# IRAMX-drv-v2.net
KiCad netlist of a schematic drawn in EAGLE
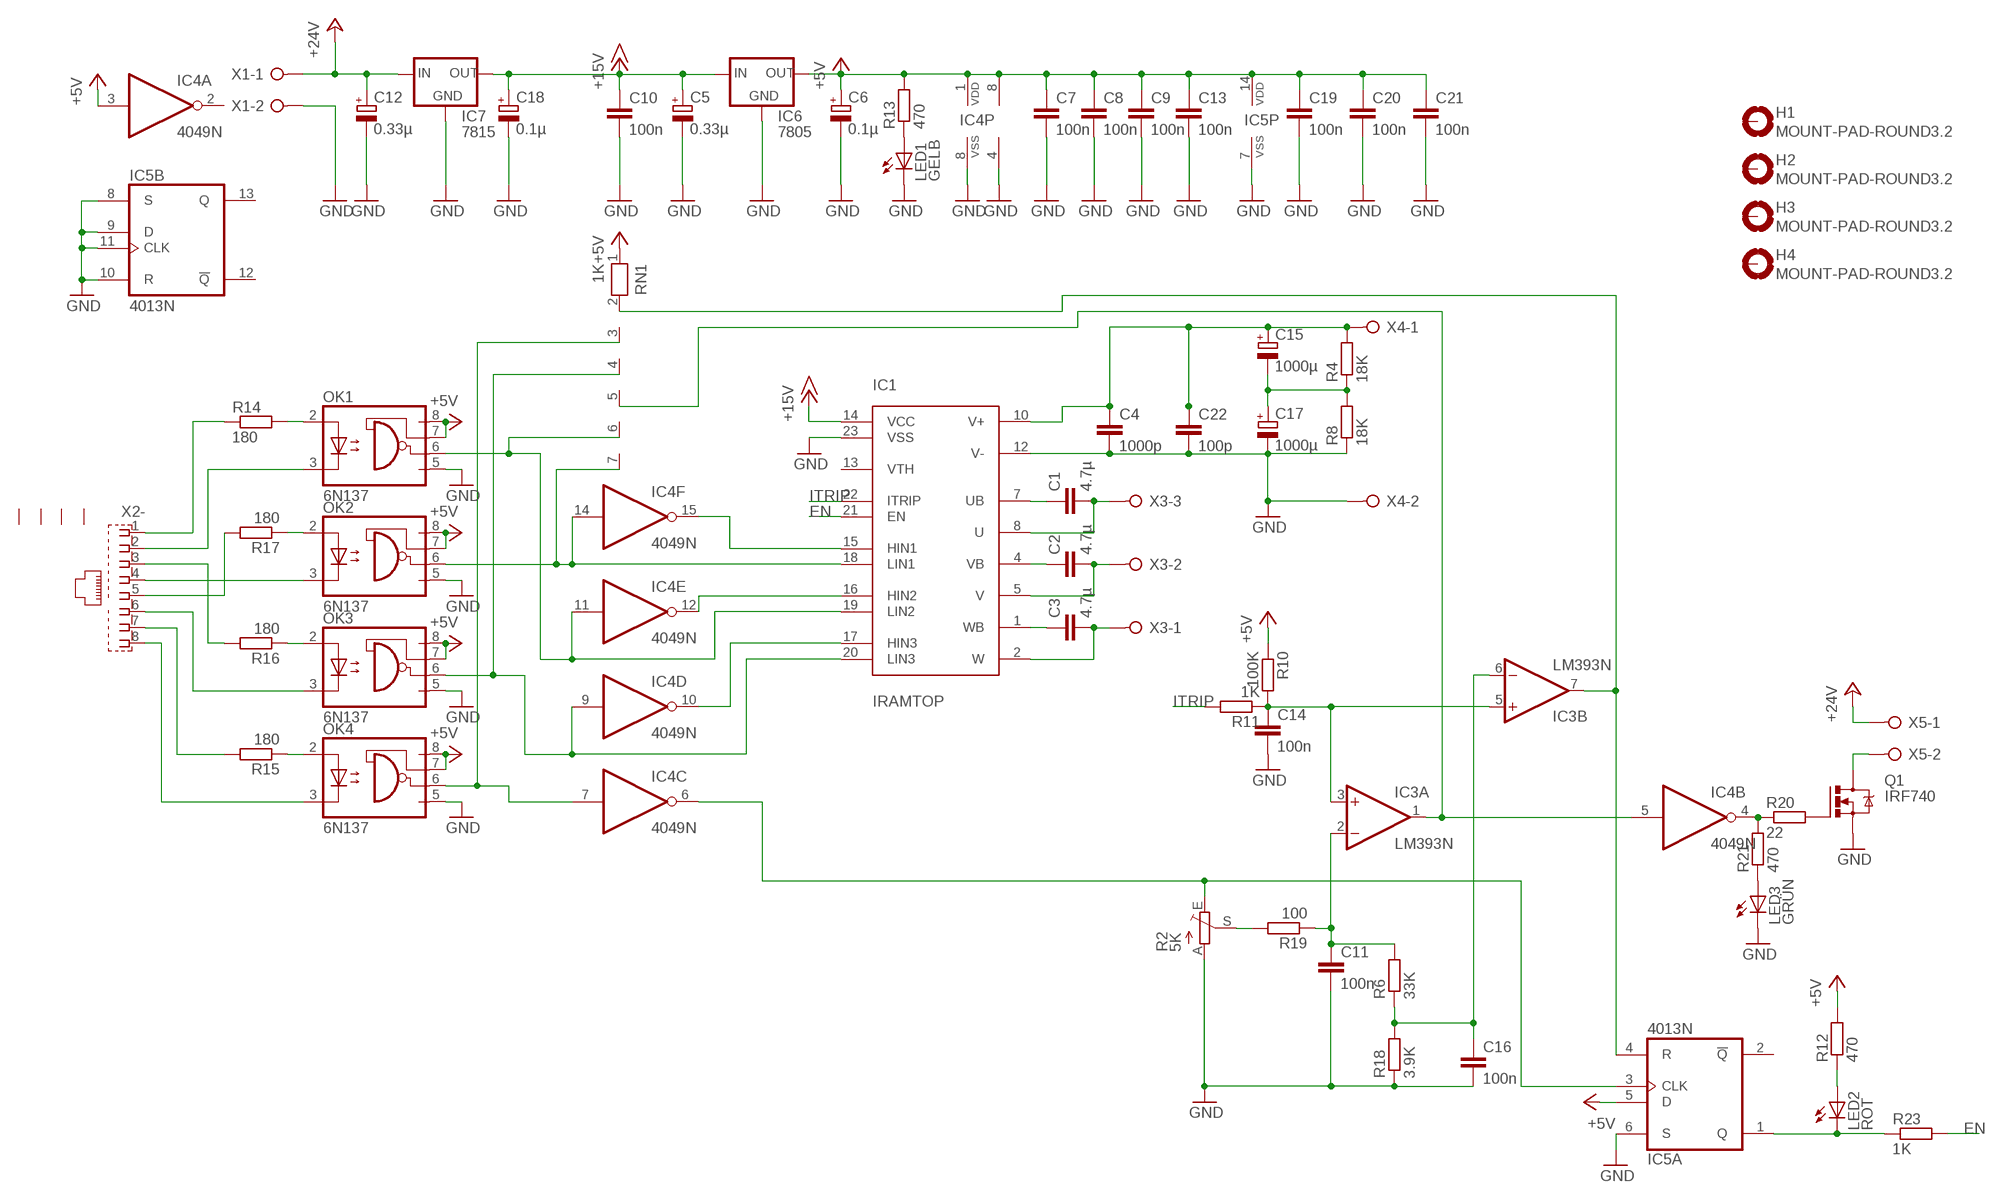
[diagram p0: schematic, sheet 1]

(export (version "E")
  (design (tool "Eeschema 10.0.6"))
  (components
    (comp (ref "C1")
      (value "4.7µ")
      (footprint "eagle-import:C5B7.2")
      (libsource (lib "eagle-import") (part "C5/7.2"))
    )
    (comp (ref "C2")
      (value "4.7µ")
      (footprint "eagle-import:C5B7.2")
      (libsource (lib "eagle-import") (part "C5/7.2"))
    )
    (comp (ref "C3")
      (value "4.7µ")
      (footprint "eagle-import:C5B7.2")
      (libsource (lib "eagle-import") (part "C5/7.2"))
    )
    (comp (ref "C4")
      (value "1000p")
      (footprint "eagle-import:C5B5")
      (libsource (lib "eagle-import") (part "C5/5"))
    )
    (comp (ref "C5")
      (value "0.33µ")
      (footprint "eagle-import:E2,5-5")
      (libsource (lib "eagle-import") (part "CPOL-EUE2.5-5"))
    )
    (comp (ref "C6")
      (value "0.1µ")
      (footprint "eagle-import:E2,5-5")
      (libsource (lib "eagle-import") (part "CPOL-EUE2.5-5"))
    )
    (comp (ref "C7")
      (value "100n")
      (footprint "eagle-import:C050-025X075")
      (libsource (lib "eagle-import") (part "C-EU050-025X075"))
    )
    (comp (ref "C8")
      (value "100n")
      (footprint "eagle-import:C050-025X075")
      (libsource (lib "eagle-import") (part "C-EU050-025X075"))
    )
    (comp (ref "C9")
      (value "100n")
      (footprint "eagle-import:C050-025X075")
      (libsource (lib "eagle-import") (part "C-EU050-025X075"))
    )
    (comp (ref "C10")
      (value "100n")
      (footprint "eagle-import:C050-025X075")
      (libsource (lib "eagle-import") (part "C-EU050-025X075"))
    )
    (comp (ref "C11")
      (value "100n")
      (footprint "eagle-import:C050-025X075")
      (libsource (lib "eagle-import") (part "C-EU050-025X075"))
    )
    (comp (ref "C12")
      (value "0.33µ")
      (footprint "eagle-import:E2,5-5")
      (libsource (lib "eagle-import") (part "CPOL-EUE2.5-5"))
    )
    (comp (ref "C13")
      (value "100n")
      (footprint "eagle-import:C050-025X075")
      (libsource (lib "eagle-import") (part "C-EU050-025X075"))
    )
    (comp (ref "C14")
      (value "100n")
      (footprint "eagle-import:C050-025X075")
      (libsource (lib "eagle-import") (part "C-EU050-025X075"))
    )
    (comp (ref "C15")
      (value "1000µ")
      (footprint "eagle-import:EB25D")
      (libsource (lib "eagle-import") (part "CPOL-EUE10-25"))
    )
    (comp (ref "C16")
      (value "100n")
      (footprint "eagle-import:C050-025X075")
      (libsource (lib "eagle-import") (part "C-EU050-025X075"))
    )
    (comp (ref "C17")
      (value "1000µ")
      (footprint "eagle-import:EB25D")
      (libsource (lib "eagle-import") (part "CPOL-EUE10-25"))
    )
    (comp (ref "C18")
      (value "0.1µ")
      (footprint "eagle-import:E2,5-5")
      (libsource (lib "eagle-import") (part "CPOL-EUE2.5-5"))
    )
    (comp (ref "C19")
      (value "100n")
      (footprint "eagle-import:C050-025X075")
      (libsource (lib "eagle-import") (part "C-EU050-025X075"))
    )
    (comp (ref "C20")
      (value "100n")
      (footprint "eagle-import:C050-025X075")
      (libsource (lib "eagle-import") (part "C-EU050-025X075"))
    )
    (comp (ref "C21")
      (value "100n")
      (footprint "eagle-import:C050-025X075")
      (libsource (lib "eagle-import") (part "C-EU050-025X075"))
    )
    (comp (ref "C22")
      (value "100p")
      (footprint "eagle-import:C150-054X183")
      (libsource (lib "eagle-import") (part "C-EU150-054X183"))
    )
    (comp (ref "H1")
      (value "MOUNT-PAD-ROUND3.2")
      (footprint "eagle-import:3,2-PAD")
      (libsource (lib "eagle-import") (part "MOUNT-PAD-ROUND3.2"))
    )
    (comp (ref "H2")
      (value "MOUNT-PAD-ROUND3.2")
      (footprint "eagle-import:3,2-PAD")
      (libsource (lib "eagle-import") (part "MOUNT-PAD-ROUND3.2"))
    )
    (comp (ref "H3")
      (value "MOUNT-PAD-ROUND3.2")
      (footprint "eagle-import:3,2-PAD")
      (libsource (lib "eagle-import") (part "MOUNT-PAD-ROUND3.2"))
    )
    (comp (ref "H4")
      (value "MOUNT-PAD-ROUND3.2")
      (footprint "eagle-import:3,2-PAD")
      (libsource (lib "eagle-import") (part "MOUNT-PAD-ROUND3.2"))
    )
    (comp (ref "IC1")
      (value "IRAMTOP")
      (footprint "eagle-import:SIP23_TOP")
      (libsource (lib "eagle-import") (part "IRAMTOP"))
    )
    (comp (ref "IC3")
      (value "LM393N")
      (footprint "eagle-import:DIL08")
      (libsource (lib "eagle-import") (part "LM393N"))
    )
    (comp (ref "IC4")
      (value "4049N")
      (footprint "eagle-import:DIL16")
      (libsource (lib "eagle-import") (part "4049N"))
    )
    (comp (ref "IC5")
      (value "4013N")
      (footprint "eagle-import:DIL14")
      (libsource (lib "eagle-import") (part "4013N"))
    )
    (comp (ref "IC6")
      (value "7805")
      (footprint "eagle-import:78XXS")
      (libsource (lib "eagle-import") (part "78XXS"))
    )
    (comp (ref "IC7")
      (value "7815")
      (footprint "eagle-import:78XXS")
      (libsource (lib "eagle-import") (part "78XXS"))
    )
    (comp (ref "LED1")
      (value "GELB")
      (footprint "eagle-import:LED5MM")
      (libsource (lib "eagle-import") (part "LED5MM"))
    )
    (comp (ref "LED2")
      (value "ROT")
      (footprint "eagle-import:LED5MM")
      (libsource (lib "eagle-import") (part "LED5MM"))
    )
    (comp (ref "LED3")
      (value "GRÜN")
      (footprint "eagle-import:LED5MM")
      (libsource (lib "eagle-import") (part "LED5MM"))
    )
    (comp (ref "OK1")
      (value "6N137")
      (footprint "eagle-import:DIL08")
      (libsource (lib "eagle-import") (part "6N137"))
    )
    (comp (ref "OK2")
      (value "6N137")
      (footprint "eagle-import:DIL08")
      (libsource (lib "eagle-import") (part "6N137"))
    )
    (comp (ref "OK3")
      (value "6N137")
      (footprint "eagle-import:DIL08")
      (libsource (lib "eagle-import") (part "6N137"))
    )
    (comp (ref "OK4")
      (value "6N137")
      (footprint "eagle-import:DIL08")
      (libsource (lib "eagle-import") (part "6N137"))
    )
    (comp (ref "Q1")
      (value "IRF740")
      (footprint "eagle-import:TO220BV")
      (libsource (lib "eagle-import") (part "IRF740"))
    )
    (comp (ref "R2")
      (value "5K")
      (footprint "eagle-import:CA6V")
      (libsource (lib "eagle-import") (part "TRIM_EU-CA6V"))
    )
    (comp (ref "R4")
      (value "18K")
      (footprint "eagle-import:CER")
      (libsource (lib "eagle-import") (part "R-EU_"))
    )
    (comp (ref "R6")
      (value "33K")
      (footprint "eagle-import:0204_7")
      (libsource (lib "eagle-import") (part "R-EU_0204/7"))
    )
    (comp (ref "R8")
      (value "18K")
      (footprint "eagle-import:CER")
      (libsource (lib "eagle-import") (part "R-EU_"))
    )
    (comp (ref "R10")
      (value "100K")
      (footprint "eagle-import:0204_7")
      (libsource (lib "eagle-import") (part "R-EU_0204/7"))
    )
    (comp (ref "R11")
      (value "1K")
      (footprint "eagle-import:0204_7")
      (libsource (lib "eagle-import") (part "R-EU_0204/7"))
    )
    (comp (ref "R12")
      (value "470")
      (footprint "eagle-import:0204_7")
      (libsource (lib "eagle-import") (part "R-EU_0204/7"))
    )
    (comp (ref "R13")
      (value "470")
      (footprint "eagle-import:0204_7")
      (libsource (lib "eagle-import") (part "R-EU_0204/7"))
    )
    (comp (ref "R14")
      (value "180")
      (footprint "eagle-import:0204V")
      (libsource (lib "eagle-import") (part "R-EU_0204/2V"))
    )
    (comp (ref "R15")
      (value "180")
      (footprint "eagle-import:0204V")
      (libsource (lib "eagle-import") (part "R-EU_0204/2V"))
    )
    (comp (ref "R16")
      (value "180")
      (footprint "eagle-import:0204V")
      (libsource (lib "eagle-import") (part "R-EU_0204/2V"))
    )
    (comp (ref "R17")
      (value "180")
      (footprint "eagle-import:0204V")
      (libsource (lib "eagle-import") (part "R-EU_0204/2V"))
    )
    (comp (ref "R18")
      (value "3.9K")
      (footprint "eagle-import:0204_7")
      (libsource (lib "eagle-import") (part "R-EU_0204/7"))
    )
    (comp (ref "R19")
      (value "100")
      (footprint "eagle-import:0204_7")
      (libsource (lib "eagle-import") (part "R-EU_0204/7"))
    )
    (comp (ref "R20")
      (value "22")
      (footprint "eagle-import:0204_7")
      (libsource (lib "eagle-import") (part "R-EU_0204/7"))
    )
    (comp (ref "R21")
      (value "470")
      (footprint "eagle-import:0204_7")
      (libsource (lib "eagle-import") (part "R-EU_0204/7"))
    )
    (comp (ref "R23")
      (value "1K")
      (footprint "eagle-import:0204_7")
      (libsource (lib "eagle-import") (part "R-EU_0204/7"))
    )
    (comp (ref "RN1")
      (value "1K")
      (footprint "eagle-import:RN-7")
      (libsource (lib "eagle-import") (part "RN06"))
    )
    (comp (ref "X1")
      (value "W237-02P")
      (footprint "eagle-import:W237-132")
      (libsource (lib "eagle-import") (part "W237-02P"))
    )
    (comp (ref "X2")
      (value "RJ45")
      (footprint "eagle-import:RJ45")
      (libsource (lib "eagle-import") (part "RJ45"))
    )
    (comp (ref "X3")
      (value "W237-03P")
      (footprint "eagle-import:W237-133")
      (libsource (lib "eagle-import") (part "W237-03P"))
    )
    (comp (ref "X4")
      (value "W237-02P")
      (footprint "eagle-import:W237-132")
      (libsource (lib "eagle-import") (part "W237-02P"))
    )
    (comp (ref "X5")
      (value "W237-02P")
      (footprint "eagle-import:W237-132")
      (libsource (lib "eagle-import") (part "W237-02P"))
    )
  )
  (nets
    (net (code "1") (name "+5V") (class "Default")
      (node (ref "C13") (pin "1") (pinfunction "1_1") (pintype "passive"))
      (node (ref "C19") (pin "1") (pinfunction "1_1") (pintype "passive"))
      (node (ref "C20") (pin "1") (pinfunction "1_1") (pintype "passive"))
      (node (ref "C21") (pin "1") (pinfunction "1_1") (pintype "passive"))
      (node (ref "C6") (pin "+") (pinfunction "+_+") (pintype "passive"))
      (node (ref "C7") (pin "1") (pinfunction "1_1") (pintype "passive"))
      (node (ref "C8") (pin "1") (pinfunction "1_1") (pintype "passive"))
      (node (ref "C9") (pin "1") (pinfunction "1_1") (pintype "passive"))
      (node (ref "IC3") (pin "8") (pinfunction "V+_8") (pintype "power_in"))
      (node (ref "IC4") (pin "1") (pinfunction "VDD_1") (pintype "power_in"))
      (node (ref "IC4") (pin "3") (pinfunction "I_3") (pintype "input"))
      (node (ref "IC5") (pin "14") (pinfunction "VDD_14") (pintype "power_in"))
      (node (ref "IC5") (pin "5") (pinfunction "D_5") (pintype "input"))
      (node (ref "IC6") (pin "OUT") (pinfunction "OUT_OUT") (pintype "passive"))
      (node (ref "OK1") (pin "7") (pinfunction "VE_7") (pintype "passive"))
      (node (ref "OK1") (pin "8") (pinfunction "VCC_8") (pintype "passive"))
      (node (ref "OK2") (pin "7") (pinfunction "VE_7") (pintype "passive"))
      (node (ref "OK2") (pin "8") (pinfunction "VCC_8") (pintype "passive"))
      (node (ref "OK3") (pin "7") (pinfunction "VE_7") (pintype "passive"))
      (node (ref "OK3") (pin "8") (pinfunction "VCC_8") (pintype "passive"))
      (node (ref "OK4") (pin "7") (pinfunction "VE_7") (pintype "passive"))
      (node (ref "OK4") (pin "8") (pinfunction "VCC_8") (pintype "passive"))
      (node (ref "R10") (pin "1") (pinfunction "1_1") (pintype "passive"))
      (node (ref "R12") (pin "2") (pinfunction "2_2") (pintype "passive"))
      (node (ref "R13") (pin "2") (pinfunction "2_2") (pintype "passive"))
      (node (ref "RN1") (pin "1") (pinfunction "1_1") (pintype "passive"))
    )
    (net (code "2") (name "+15V") (class "Default")
      (node (ref "C10") (pin "1") (pinfunction "1_1") (pintype "passive"))
      (node (ref "C18") (pin "+") (pinfunction "+_+") (pintype "passive"))
      (node (ref "C5") (pin "+") (pinfunction "+_+") (pintype "passive"))
      (node (ref "IC1") (pin "14") (pinfunction "VCC_14") (pintype "bidirectional"))
      (node (ref "IC6") (pin "IN") (pinfunction "IN_IN") (pintype "input"))
      (node (ref "IC7") (pin "OUT") (pinfunction "OUT_OUT") (pintype "passive"))
    )
    (net (code "3") (name "+24V") (class "Default")
      (node (ref "C12") (pin "+") (pinfunction "+_+") (pintype "passive"))
      (node (ref "IC7") (pin "IN") (pinfunction "IN_IN") (pintype "input"))
      (node (ref "X1") (pin "1") (pinfunction "KL_1") (pintype "passive"))
      (node (ref "X5") (pin "1") (pinfunction "KL_1") (pintype "passive"))
    )
    (net (code "4") (name "/EN") (class "Default")
      (node (ref "IC1") (pin "21") (pinfunction "EN_21") (pintype "bidirectional"))
      (node (ref "R23") (pin "2") (pinfunction "2_2") (pintype "passive"))
    )
    (net (code "5") (name "/ITRIP") (class "Default")
      (node (ref "IC1") (pin "22") (pinfunction "ITRIP_22") (pintype "bidirectional"))
      (node (ref "R11") (pin "2") (pinfunction "2_2") (pintype "passive"))
    )
    (net (code "6") (name "GND") (class "Default")
      (node (ref "C10") (pin "2") (pinfunction "2_2") (pintype "passive"))
      (node (ref "C11") (pin "2") (pinfunction "2_2") (pintype "passive"))
      (node (ref "C12") (pin "-") (pinfunction "-_-") (pintype "passive"))
      (node (ref "C13") (pin "2") (pinfunction "2_2") (pintype "passive"))
      (node (ref "C14") (pin "2") (pinfunction "2_2") (pintype "passive"))
      (node (ref "C16") (pin "2") (pinfunction "2_2") (pintype "passive"))
      (node (ref "C17") (pin "-") (pinfunction "-_-") (pintype "passive"))
      (node (ref "C18") (pin "-") (pinfunction "-_-") (pintype "passive"))
      (node (ref "C19") (pin "2") (pinfunction "2_2") (pintype "passive"))
      (node (ref "C20") (pin "2") (pinfunction "2_2") (pintype "passive"))
      (node (ref "C21") (pin "2") (pinfunction "2_2") (pintype "passive"))
      (node (ref "C22") (pin "2") (pinfunction "2_2") (pintype "passive"))
      (node (ref "C4") (pin "2") (pinfunction "2_2") (pintype "passive"))
      (node (ref "C5") (pin "-") (pinfunction "-_-") (pintype "passive"))
      (node (ref "C6") (pin "-") (pinfunction "-_-") (pintype "passive"))
      (node (ref "C7") (pin "2") (pinfunction "2_2") (pintype "passive"))
      (node (ref "C8") (pin "2") (pinfunction "2_2") (pintype "passive"))
      (node (ref "C9") (pin "2") (pinfunction "2_2") (pintype "passive"))
      (node (ref "IC1") (pin "12") (pinfunction "V-_12") (pintype "bidirectional"))
      (node (ref "IC1") (pin "23") (pinfunction "VSS_23") (pintype "bidirectional"))
      (node (ref "IC3") (pin "4") (pinfunction "V-_4") (pintype "power_in"))
      (node (ref "IC4") (pin "8") (pinfunction "VSS_8") (pintype "power_in"))
      (node (ref "IC5") (pin "10") (pinfunction "R_10") (pintype "input"))
      (node (ref "IC5") (pin "11") (pinfunction "CLK_11") (pintype "input"))
      (node (ref "IC5") (pin "6") (pinfunction "S_6") (pintype "input"))
      (node (ref "IC5") (pin "7") (pinfunction "VSS_7") (pintype "power_in"))
      (node (ref "IC5") (pin "8") (pinfunction "S_8") (pintype "input"))
      (node (ref "IC5") (pin "9") (pinfunction "D_9") (pintype "input"))
      (node (ref "IC6") (pin "GND") (pinfunction "GND_GND") (pintype "input"))
      (node (ref "IC7") (pin "GND") (pinfunction "GND_GND") (pintype "input"))
      (node (ref "LED1") (pin "K") (pinfunction "C_K") (pintype "passive"))
      (node (ref "LED3") (pin "K") (pinfunction "C_K") (pintype "passive"))
      (node (ref "OK1") (pin "5") (pinfunction "GND_5") (pintype "passive"))
      (node (ref "OK2") (pin "5") (pinfunction "GND_5") (pintype "passive"))
      (node (ref "OK3") (pin "5") (pinfunction "GND_5") (pintype "passive"))
      (node (ref "OK4") (pin "5") (pinfunction "GND_5") (pintype "passive"))
      (node (ref "Q1") (pin "S") (pinfunction "S_S") (pintype "passive"))
      (node (ref "R18") (pin "1") (pinfunction "1_1") (pintype "passive"))
      (node (ref "R2") (pin "A") (pinfunction "A_A") (pintype "passive"))
      (node (ref "R8") (pin "P$1") (pinfunction "1_P$1") (pintype "passive"))
      (node (ref "X1") (pin "2") (pinfunction "KL_2") (pintype "passive"))
      (node (ref "X4") (pin "2") (pinfunction "KL_2") (pintype "passive"))
    )
    (net (code "7") (name "Net-(IC1-HIN1)") (class "Default")
      (node (ref "IC1") (pin "15") (pinfunction "HIN1_15") (pintype "bidirectional"))
      (node (ref "IC4") (pin "15") (pinfunction "O_15") (pintype "output"))
    )
    (net (code "8") (name "Net-(IC1-HIN2)") (class "Default")
      (node (ref "IC1") (pin "16") (pinfunction "HIN2_16") (pintype "bidirectional"))
      (node (ref "IC4") (pin "12") (pinfunction "O_12") (pintype "output"))
    )
    (net (code "9") (name "Net-(IC1-HIN3)") (class "Default")
      (node (ref "IC1") (pin "17") (pinfunction "HIN3_17") (pintype "bidirectional"))
      (node (ref "IC4") (pin "10") (pinfunction "O_10") (pintype "output"))
    )
    (net (code "10") (name "Net-(IC1-LIN1)") (class "Default")
      (node (ref "IC1") (pin "18") (pinfunction "LIN1_18") (pintype "bidirectional"))
      (node (ref "IC4") (pin "14") (pinfunction "I_14") (pintype "input"))
      (node (ref "OK2") (pin "6") (pinfunction "VO_6") (pintype "passive"))
      (node (ref "RN1") (pin "7") (pinfunction "7_7") (pintype "passive"))
    )
    (net (code "11") (name "Net-(IC1-LIN2)") (class "Default")
      (node (ref "IC1") (pin "19") (pinfunction "LIN2_19") (pintype "bidirectional"))
      (node (ref "IC4") (pin "11") (pinfunction "I_11") (pintype "input"))
      (node (ref "OK1") (pin "6") (pinfunction "VO_6") (pintype "passive"))
      (node (ref "RN1") (pin "6") (pinfunction "6_6") (pintype "passive"))
    )
    (net (code "12") (name "Net-(IC1-LIN3)") (class "Default")
      (node (ref "IC1") (pin "20") (pinfunction "LIN3_20") (pintype "bidirectional"))
      (node (ref "IC4") (pin "9") (pinfunction "I_9") (pintype "input"))
      (node (ref "OK3") (pin "6") (pinfunction "VO_6") (pintype "passive"))
      (node (ref "RN1") (pin "4") (pinfunction "4_4") (pintype "passive"))
    )
    (net (code "13") (name "Net-(IC1-U)") (class "Default")
      (node (ref "C1") (pin "2") (pinfunction "2_2") (pintype "passive"))
      (node (ref "IC1") (pin "8") (pinfunction "U_8") (pintype "bidirectional"))
      (node (ref "X3") (pin "3") (pinfunction "KL_3") (pintype "passive"))
    )
    (net (code "14") (name "Net-(IC1-UB)") (class "Default")
      (node (ref "C1") (pin "1") (pinfunction "1_1") (pintype "passive"))
      (node (ref "IC1") (pin "7") (pinfunction "UB_7") (pintype "bidirectional"))
    )
    (net (code "15") (name "Net-(IC1-V)") (class "Default")
      (node (ref "C2") (pin "2") (pinfunction "2_2") (pintype "passive"))
      (node (ref "IC1") (pin "5") (pinfunction "V_5") (pintype "bidirectional"))
      (node (ref "X3") (pin "2") (pinfunction "KL_2") (pintype "passive"))
    )
    (net (code "16") (name "Net-(IC1-V+)") (class "Default")
      (node (ref "C15") (pin "+") (pinfunction "+_+") (pintype "passive"))
      (node (ref "C22") (pin "1") (pinfunction "1_1") (pintype "passive"))
      (node (ref "C4") (pin "1") (pinfunction "1_1") (pintype "passive"))
      (node (ref "IC1") (pin "10") (pinfunction "V+_10") (pintype "bidirectional"))
      (node (ref "R4") (pin "P$2") (pinfunction "2_P$2") (pintype "passive"))
      (node (ref "X4") (pin "1") (pinfunction "KL_1") (pintype "passive"))
    )
    (net (code "17") (name "Net-(IC1-VB)") (class "Default")
      (node (ref "C2") (pin "1") (pinfunction "1_1") (pintype "passive"))
      (node (ref "IC1") (pin "4") (pinfunction "VB_4") (pintype "bidirectional"))
    )
    (net (code "18") (name "Net-(IC1-W)") (class "Default")
      (node (ref "C3") (pin "2") (pinfunction "2_2") (pintype "passive"))
      (node (ref "IC1") (pin "2") (pinfunction "W_2") (pintype "bidirectional"))
      (node (ref "X3") (pin "1") (pinfunction "KL_1") (pintype "passive"))
    )
    (net (code "19") (name "Net-(IC1-WB)") (class "Default")
      (node (ref "C3") (pin "1") (pinfunction "1_1") (pintype "passive"))
      (node (ref "IC1") (pin "1") (pinfunction "WB_1") (pintype "bidirectional"))
    )
    (net (code "20") (name "Net-(IC3A-+IN)") (class "Default")
      (node (ref "C14") (pin "1") (pinfunction "1_1") (pintype "passive"))
      (node (ref "IC3") (pin "3") (pinfunction "+IN_3") (pintype "input"))
      (node (ref "IC3") (pin "5") (pinfunction "+IN_5") (pintype "input"))
      (node (ref "R10") (pin "2") (pinfunction "2_2") (pintype "passive"))
      (node (ref "R11") (pin "1") (pinfunction "1_1") (pintype "passive"))
    )
    (net (code "21") (name "Net-(IC3A--IN)") (class "Default")
      (node (ref "C11") (pin "1") (pinfunction "1_1") (pintype "passive"))
      (node (ref "IC3") (pin "2") (pinfunction "-IN_2") (pintype "input"))
      (node (ref "R19") (pin "1") (pinfunction "1_1") (pintype "passive"))
      (node (ref "R6") (pin "2") (pinfunction "2_2") (pintype "passive"))
    )
    (net (code "22") (name "Net-(IC3A-OUT)") (class "Default")
      (node (ref "IC3") (pin "1") (pinfunction "OUT_1") (pintype "output"))
      (node (ref "IC4") (pin "5") (pinfunction "I_5") (pintype "input"))
      (node (ref "RN1") (pin "5") (pinfunction "5_5") (pintype "passive"))
    )
    (net (code "23") (name "Net-(IC3B--IN)") (class "Default")
      (node (ref "C16") (pin "1") (pinfunction "1_1") (pintype "passive"))
      (node (ref "IC3") (pin "6") (pinfunction "-IN_6") (pintype "input"))
      (node (ref "R18") (pin "2") (pinfunction "2_2") (pintype "passive"))
      (node (ref "R6") (pin "1") (pinfunction "1_1") (pintype "passive"))
    )
    (net (code "24") (name "Net-(IC3B-OUT)") (class "Default")
      (node (ref "IC3") (pin "7") (pinfunction "OUT_7") (pintype "output"))
      (node (ref "IC5") (pin "4") (pinfunction "R_4") (pintype "input"))
      (node (ref "RN1") (pin "2") (pinfunction "2_2") (pintype "passive"))
    )
    (net (code "25") (name "Net-(IC4B-O)") (class "Default")
      (node (ref "IC4") (pin "4") (pinfunction "O_4") (pintype "output"))
      (node (ref "R20") (pin "1") (pinfunction "1_1") (pintype "passive"))
      (node (ref "R21") (pin "2") (pinfunction "2_2") (pintype "passive"))
    )
    (net (code "26") (name "Net-(IC4C-I)") (class "Default")
      (node (ref "IC4") (pin "7") (pinfunction "I_7") (pintype "input"))
      (node (ref "OK4") (pin "6") (pinfunction "VO_6") (pintype "passive"))
      (node (ref "RN1") (pin "3") (pinfunction "3_3") (pintype "passive"))
    )
    (net (code "27") (name "Net-(IC4C-O)") (class "Default")
      (node (ref "IC4") (pin "6") (pinfunction "O_6") (pintype "output"))
      (node (ref "IC5") (pin "3") (pinfunction "CLK_3") (pintype "input"))
      (node (ref "R2") (pin "E") (pinfunction "E_E") (pintype "passive"))
    )
    (net (code "28") (name "Net-(IC5A-Q)") (class "Default")
      (node (ref "IC5") (pin "1") (pinfunction "Q_1") (pintype "output"))
      (node (ref "LED2") (pin "K") (pinfunction "C_K") (pintype "passive"))
      (node (ref "R23") (pin "1") (pinfunction "1_1") (pintype "passive"))
    )
    (net (code "29") (name "Net-(LED1-PadA)") (class "Default")
      (node (ref "LED1") (pin "A") (pinfunction "A_A") (pintype "passive"))
      (node (ref "R13") (pin "1") (pinfunction "1_1") (pintype "passive"))
    )
    (net (code "30") (name "Net-(LED2-PadA)") (class "Default")
      (node (ref "LED2") (pin "A") (pinfunction "A_A") (pintype "passive"))
      (node (ref "R12") (pin "1") (pinfunction "1_1") (pintype "passive"))
    )
    (net (code "31") (name "Net-(LED3-PadA)") (class "Default")
      (node (ref "LED3") (pin "A") (pinfunction "A_A") (pintype "passive"))
      (node (ref "R21") (pin "1") (pinfunction "1_1") (pintype "passive"))
    )
    (net (code "32") (name "Net-(OK1-A)") (class "Default")
      (node (ref "OK1") (pin "2") (pinfunction "A_2") (pintype "passive"))
      (node (ref "R14") (pin "2") (pinfunction "2_2") (pintype "passive"))
    )
    (net (code "33") (name "Net-(OK1-C)") (class "Default")
      (node (ref "OK1") (pin "3") (pinfunction "C_3") (pintype "passive"))
      (node (ref "X2") (pin "2") (pinfunction "2_2") (pintype "passive"))
    )
    (net (code "34") (name "Net-(OK2-A)") (class "Default")
      (node (ref "OK2") (pin "2") (pinfunction "A_2") (pintype "passive"))
      (node (ref "R17") (pin "1") (pinfunction "1_1") (pintype "passive"))
    )
    (net (code "35") (name "Net-(OK2-C)") (class "Default")
      (node (ref "OK2") (pin "3") (pinfunction "C_3") (pintype "passive"))
      (node (ref "X2") (pin "4") (pinfunction "4_4") (pintype "passive"))
    )
    (net (code "36") (name "Net-(OK3-A)") (class "Default")
      (node (ref "OK3") (pin "2") (pinfunction "A_2") (pintype "passive"))
      (node (ref "R16") (pin "1") (pinfunction "1_1") (pintype "passive"))
    )
    (net (code "37") (name "Net-(OK3-C)") (class "Default")
      (node (ref "OK3") (pin "3") (pinfunction "C_3") (pintype "passive"))
      (node (ref "X2") (pin "6") (pinfunction "6_6") (pintype "passive"))
    )
    (net (code "38") (name "Net-(OK4-A)") (class "Default")
      (node (ref "OK4") (pin "2") (pinfunction "A_2") (pintype "passive"))
      (node (ref "R15") (pin "1") (pinfunction "1_1") (pintype "passive"))
    )
    (net (code "39") (name "Net-(OK4-C)") (class "Default")
      (node (ref "OK4") (pin "3") (pinfunction "C_3") (pintype "passive"))
      (node (ref "X2") (pin "8") (pinfunction "8_8") (pintype "passive"))
    )
    (net (code "40") (name "Net-(Q1-PadG)") (class "Default")
      (node (ref "Q1") (pin "G") (pinfunction "G_G") (pintype "passive"))
      (node (ref "R20") (pin "2") (pinfunction "2_2") (pintype "passive"))
    )
    (net (code "41") (name "Net-(R4-1)") (class "Default")
      (node (ref "C15") (pin "-") (pinfunction "-_-") (pintype "passive"))
      (node (ref "C17") (pin "+") (pinfunction "+_+") (pintype "passive"))
      (node (ref "R4") (pin "P$1") (pinfunction "1_P$1") (pintype "passive"))
      (node (ref "R8") (pin "P$2") (pinfunction "2_P$2") (pintype "passive"))
    )
    (net (code "42") (name "Net-(R14-Pad1)") (class "Default")
      (node (ref "R14") (pin "1") (pinfunction "1_1") (pintype "passive"))
      (node (ref "X2") (pin "1") (pinfunction "1_1") (pintype "passive"))
    )
    (net (code "43") (name "Net-(R15-Pad2)") (class "Default")
      (node (ref "R15") (pin "2") (pinfunction "2_2") (pintype "passive"))
      (node (ref "X2") (pin "7") (pinfunction "7_7") (pintype "passive"))
    )
    (net (code "44") (name "Net-(R16-Pad2)") (class "Default")
      (node (ref "R16") (pin "2") (pinfunction "2_2") (pintype "passive"))
      (node (ref "X2") (pin "3") (pinfunction "3_3") (pintype "passive"))
    )
    (net (code "45") (name "Net-(R17-Pad2)") (class "Default")
      (node (ref "R17") (pin "2") (pinfunction "2_2") (pintype "passive"))
      (node (ref "X2") (pin "5") (pinfunction "5_5") (pintype "passive"))
    )
    (net (code "46") (name "Net-(R19-Pad2)") (class "Default")
      (node (ref "R19") (pin "2") (pinfunction "2_2") (pintype "passive"))
      (node (ref "R2") (pin "S") (pinfunction "S_S") (pintype "passive"))
    )
    (net (code "47") (name "Net-(X5B-KL)") (class "Default")
      (node (ref "Q1") (pin "D") (pinfunction "D_D") (pintype "passive"))
      (node (ref "X5") (pin "2") (pinfunction "KL_2") (pintype "passive"))
    )
    (net (code "48") (name "unconnected-(H1-MOUNT-PadB3,2)") (class "Default")
      (node (ref "H1") (pin "B3,2") (pinfunction "MOUNT_B3,2") (pintype "passive"))
    )
    (net (code "49") (name "unconnected-(H2-MOUNT-PadB3,2)") (class "Default")
      (node (ref "H2") (pin "B3,2") (pinfunction "MOUNT_B3,2") (pintype "passive"))
    )
    (net (code "50") (name "unconnected-(H3-MOUNT-PadB3,2)") (class "Default")
      (node (ref "H3") (pin "B3,2") (pinfunction "MOUNT_B3,2") (pintype "passive"))
    )
    (net (code "51") (name "unconnected-(H4-MOUNT-PadB3,2)") (class "Default")
      (node (ref "H4") (pin "B3,2") (pinfunction "MOUNT_B3,2") (pintype "passive"))
    )
    (net (code "52") (name "unconnected-(IC1-VTH-Pad13)") (class "Default")
      (node (ref "IC1") (pin "13") (pinfunction "VTH_13") (pintype "bidirectional"))
    )
    (net (code "53") (name "unconnected-(IC4A-O-Pad2)") (class "Default")
      (node (ref "IC4") (pin "2") (pinfunction "O_2") (pintype "output"))
    )
    (net (code "54") (name "unconnected-(IC5A-~{Q}-Pad2)") (class "Default")
      (node (ref "IC5") (pin "2") (pinfunction "~{Q}_2") (pintype "output"))
    )
    (net (code "55") (name "unconnected-(IC5B-Q-Pad13)") (class "Default")
      (node (ref "IC5") (pin "13") (pinfunction "Q_13") (pintype "output"))
    )
    (net (code "56") (name "unconnected-(IC5B-~{Q}-Pad12)") (class "Default")
      (node (ref "IC5") (pin "12") (pinfunction "~{Q}_12") (pintype "output"))
    )
    (net (code "57") (name "unconnected-(X2B-1-PadG1)") (class "Default")
      (node (ref "X2") (pin "G1") (pinfunction "1_G1") (pintype "passive"))
    )
    (net (code "58") (name "unconnected-(X2C-1-PadG2)") (class "Default")
      (node (ref "X2") (pin "G2") (pinfunction "1_G2") (pintype "passive"))
    )
    (net (code "59") (name "unconnected-(X2D-1-PadG3)") (class "Default")
      (node (ref "X2") (pin "G3") (pinfunction "1_G3") (pintype "passive"))
    )
    (net (code "60") (name "unconnected-(X2E-1-PadG4)") (class "Default")
      (node (ref "X2") (pin "G4") (pinfunction "1_G4") (pintype "passive"))
    )
  )
)
